# BT612-4.net
KiCad netlist of a schematic drawn in Altium Designer
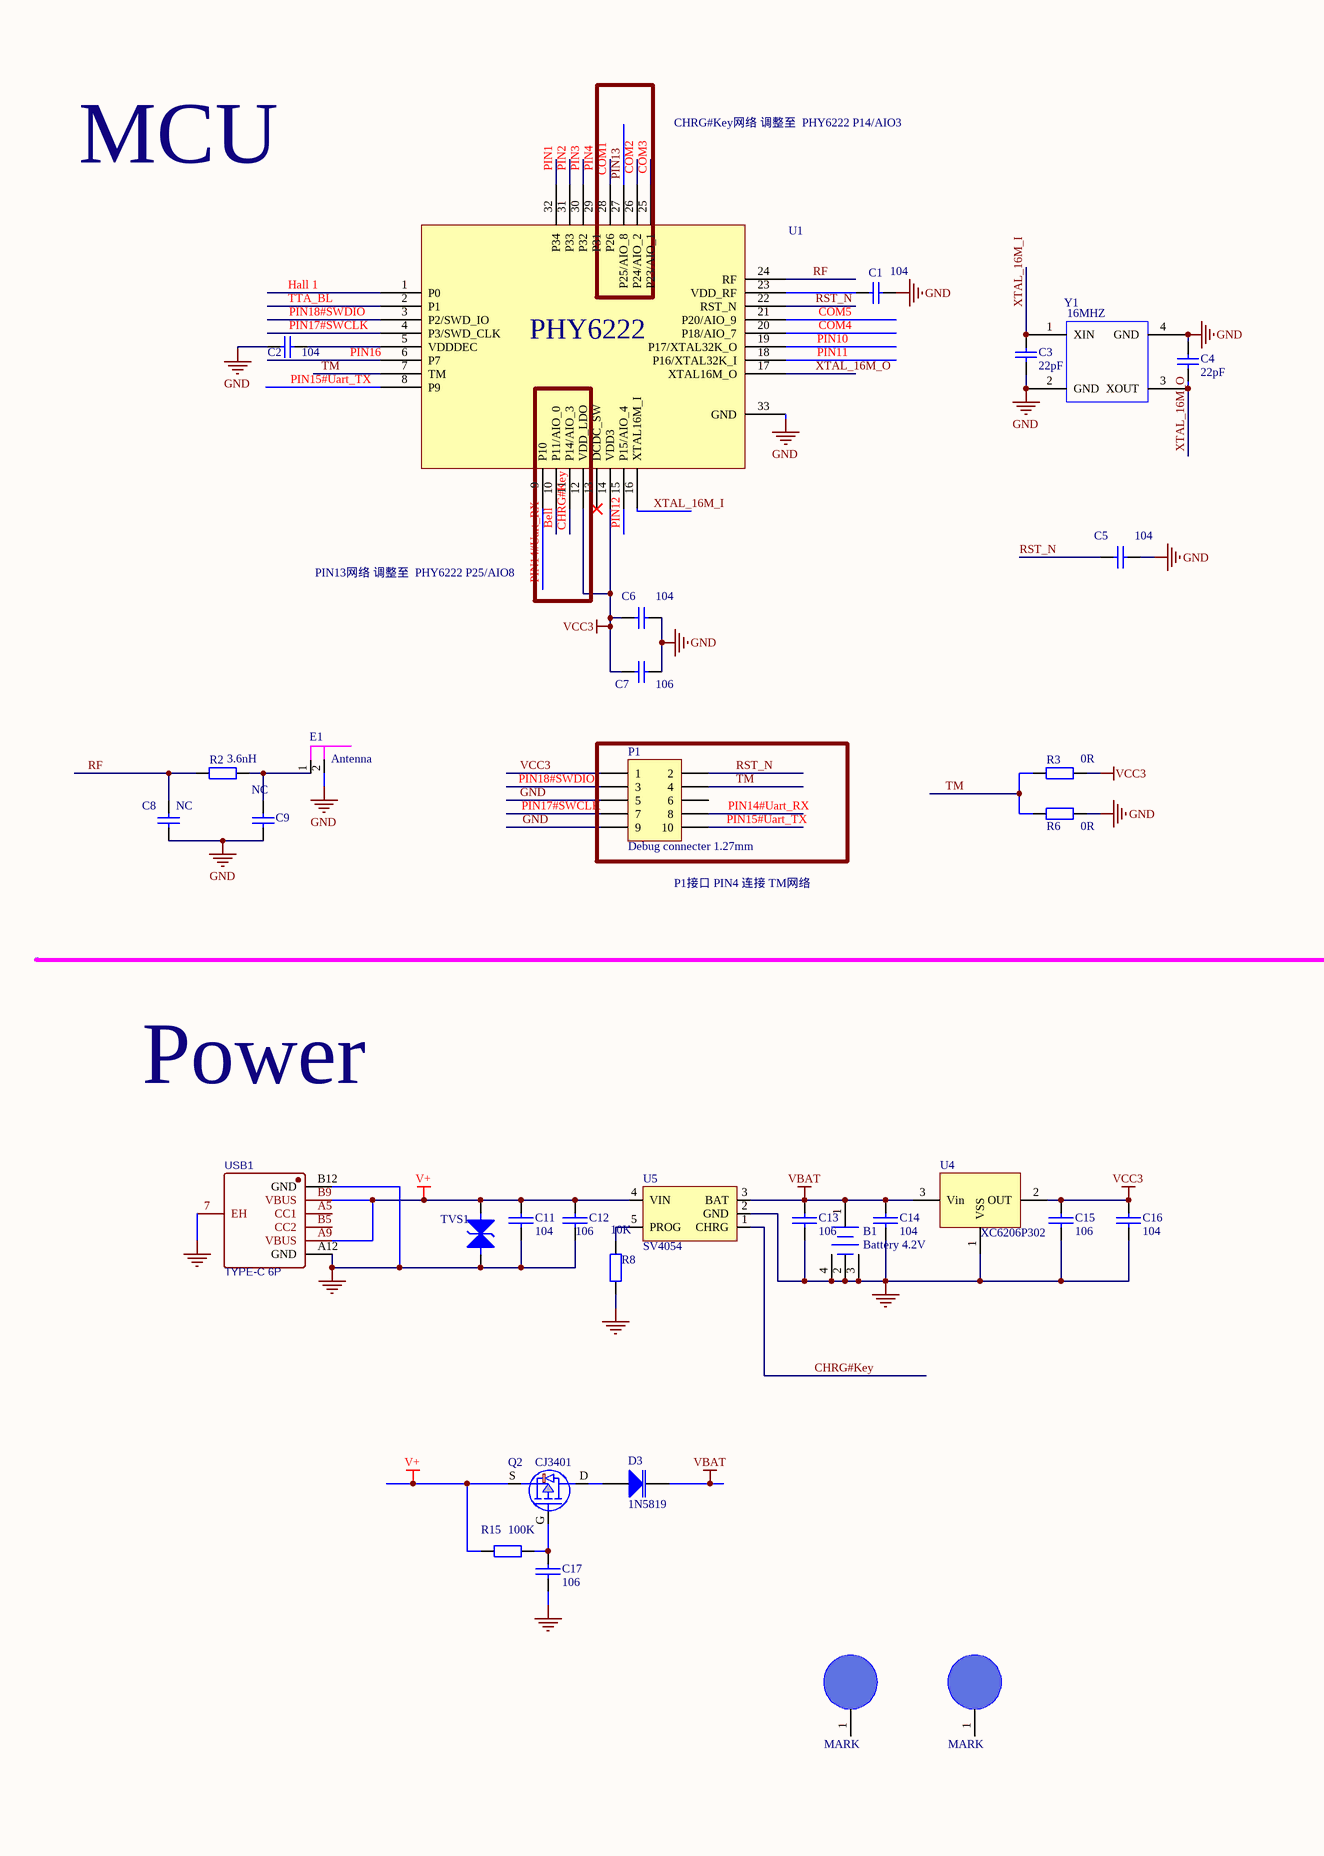
[diagram p0: BT612-4.SchDoc, left]
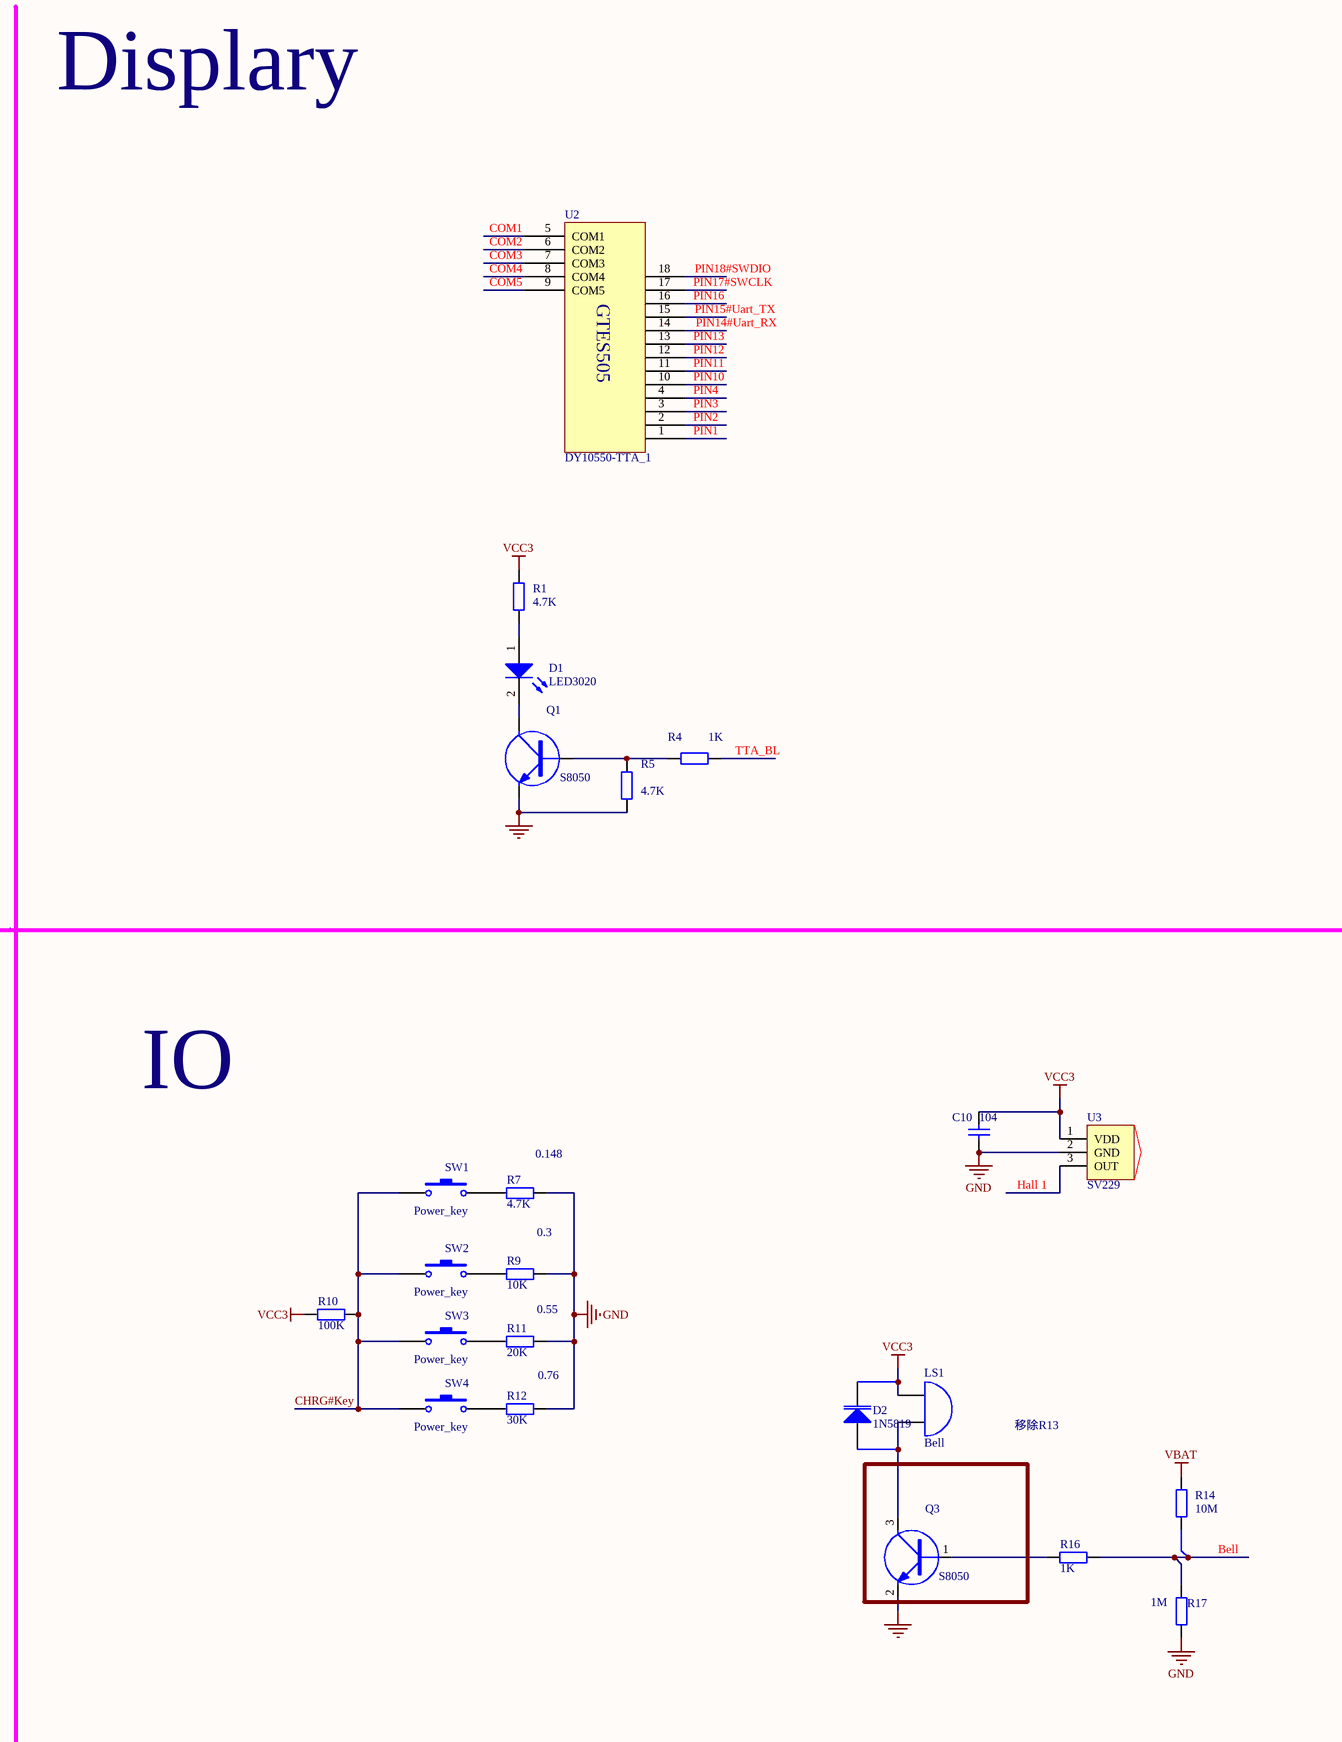
[diagram p1: BT612-4.SchDoc, right]

(export (version "E")
  (design (tool "Eeschema 10.0.6"))
  (components
    (comp (ref "B1")
      (value "Battery 4.2V")
      (footprint "BAT2P-1.25")
      (description "Multicell Battery")
      (fields (field (name "PUBLISHER") "Altium Limited"))
      (libsource (lib "SR4K_PHY6222_simplify_v1") (part "Battery"))
    )
    (comp (ref "C1")
      (value "104")
      (footprint "0402C")
      (description "Capacitor")
      (fields (field (name "PUBLISHER") "Altium Limited"))
      (libsource (lib "Miscellaneous Devices") (part "Cap"))
    )
    (comp (ref "C2")
      (value "104")
      (footprint "0402C")
      (description "Capacitor")
      (fields (field (name "PUBLISHER") "Altium Limited"))
      (libsource (lib "Miscellaneous Devices") (part "Cap"))
    )
    (comp (ref "C3")
      (value "22pF")
      (footprint "0402C")
      (description "Capacitor")
      (fields (field (name "PUBLISHER") "Altium Limited"))
      (libsource (lib "Miscellaneous Devices") (part "Cap"))
    )
    (comp (ref "C4")
      (value "22pF")
      (footprint "0402C")
      (description "Capacitor")
      (libsource (lib "Miscellaneous Devices") (part "Cap"))
    )
    (comp (ref "C5")
      (value "104")
      (footprint "0402C")
      (description "Capacitor")
      (fields (field (name "PUBLISHER") "Altium Limited"))
      (libsource (lib "Miscellaneous Devices") (part "Cap"))
    )
    (comp (ref "C6")
      (value "104")
      (footprint "0402C")
      (description "Capacitor")
      (fields (field (name "PUBLISHER") "Altium Limited"))
      (libsource (lib "Miscellaneous Devices") (part "Cap"))
    )
    (comp (ref "C7")
      (value "106")
      (footprint "0603-C")
      (description "Capacitor")
      (fields (field (name "PUBLISHER") "Altium Limited"))
      (libsource (lib "Miscellaneous Devices") (part "Cap"))
    )
    (comp (ref "C8")
      (value "NC")
      (footprint "0402C")
      (description "Capacitor")
      (fields (field (name "PUBLISHER") "Altium Limited"))
      (libsource (lib "Miscellaneous Devices") (part "Cap"))
    )
    (comp (ref "C9")
      (value "NC")
      (footprint "0402C")
      (description "Capacitor")
      (fields (field (name "PUBLISHER") "Altium Limited"))
      (libsource (lib "Miscellaneous Devices") (part "Cap"))
    )
    (comp (ref "C10")
      (value "104")
      (footprint "0402C")
      (description "Capacitor")
      (fields (field (name "PUBLISHER") "Altium Limited"))
      (libsource (lib "Miscellaneous Devices") (part "Cap"))
    )
    (comp (ref "C11")
      (value "104")
      (footprint "0402C")
      (description "Capacitor")
      (libsource (lib "*") (part "CAP"))
    )
    (comp (ref "C12")
      (value "106")
      (footprint "0603-C")
      (description "Capacitor")
      (libsource (lib "*") (part "CAP"))
    )
    (comp (ref "C13")
      (value "106")
      (footprint "0603-C")
      (description "Capacitor")
      (libsource (lib "*") (part "CAP"))
    )
    (comp (ref "C14")
      (value "104")
      (footprint "0402C")
      (description "Capacitor")
      (libsource (lib "*") (part "CAP"))
    )
    (comp (ref "C15")
      (value "106")
      (footprint "0603-C")
      (description "Capacitor")
      (libsource (lib "*") (part "CAP"))
    )
    (comp (ref "C16")
      (value "104")
      (footprint "0402C")
      (description "Capacitor")
      (libsource (lib "*") (part "CAP"))
    )
    (comp (ref "C17")
      (value "106")
      (footprint "0603-C")
      (description "Capacitor")
      (libsource (lib "*") (part "CAP"))
    )
    (comp (ref "D1")
      (value "LED3020")
      (footprint "LED-3020")
      (description "Typical INFRARED GaAs LED")
      (fields (field (name "PUBLISHER") "Altium Limited"))
      (libsource (lib "Miscellaneous Devices") (part "LED0"))
    )
    (comp (ref "D2")
      (value "1N5819")
      (footprint "SOD323")
      (description "Variable Capacitance Diode")
      (fields (field (name "PUBLISHER") "Altium Limited"))
      (libsource (lib "Miscellaneous Devices") (part "D Varactor"))
    )
    (comp (ref "D3")
      (value "1N5819")
      (footprint "SOD323")
      (description "Variable Capacitance Diode")
      (fields (field (name "PUBLISHER") "Altium Limited"))
      (libsource (lib "Miscellaneous Devices") (part "D Varactor"))
    )
    (comp (ref "E1") (value "Antenna") (footprint "BT-ANT") (libsource (lib "Schlib") (part "Antenna")))
    (comp (ref "LS1")
      (value "Bell")
      (footprint "BUZZ-12085")
      (description "Electrical Bell")
      (fields (field (name "PUBLISHER") "Altium Limited"))
      (libsource (lib "Miscellaneous Devices") (part "Bell"))
    )
    (comp (ref "P1")
      (value "Debug connecter 1.27mm")
      (footprint "SIP5-X2-1.27")
      (description "Header, 5-Pin, Dual row")
      (fields (field (name "PUBLISHER") "Altium Limited"))
      (libsource (lib "Miscellaneous Connectors") (part "Header 5X2"))
    )
    (comp (ref "Q1")
      (value "S8050")
      (footprint "SOT23")
      (description "NPN Transistor")
      (libsource (lib "*") (part "NPN"))
    )
    (comp (ref "Q2") (value "CJ3401") (footprint "SOT-23-GSD") (libsource (lib "*") (part "P-MOS")))
    (comp (ref "Q3")
      (value "S8050")
      (footprint "SOT23")
      (description "NPN Transistor")
      (libsource (lib "") (part "NPN_1"))
    )
    (comp (ref "R1")
      (value "4.7K")
      (footprint "0402R")
      (description "Resistor")
      (fields (field (name "PUBLISHER") "Altium Limited"))
      (libsource (lib "") (part "Res2_1"))
    )
    (comp (ref "R2")
      (value "3.6nH")
      (footprint "0402R")
      (description "Resistor")
      (fields (field (name "PUBLISHER") "Altium Limited"))
      (libsource (lib "") (part "Res2_2"))
    )
    (comp (ref "R3")
      (value "0R")
      (footprint "0402R")
      (description "Resistor")
      (fields (field (name "PUBLISHER") "Altium Limited"))
      (libsource (lib "") (part "Res2_2"))
    )
    (comp (ref "R4")
      (value "1K")
      (footprint "0402R")
      (description "Resistor")
      (fields (field (name "PUBLISHER") "Altium Limited"))
      (libsource (lib "Miscellaneous Devices") (part "Res2"))
    )
    (comp (ref "R5")
      (value "4.7K")
      (footprint "0402R")
      (description "Resistor")
      (fields (field (name "PUBLISHER") "Altium Limited"))
      (libsource (lib "") (part "Res2_1"))
    )
    (comp (ref "R6")
      (value "0R")
      (footprint "0402R")
      (description "Resistor")
      (fields (field (name "PUBLISHER") "Altium Limited"))
      (libsource (lib "") (part "Res2_2"))
    )
    (comp (ref "R7")
      (value "4.7K")
      (footprint "0402R")
      (description "Resistor")
      (fields (field (name "PUBLISHER") "Altium Limited"))
      (libsource (lib "Miscellaneous Devices") (part "Res2"))
    )
    (comp (ref "R8")
      (value "10K")
      (footprint "0402R")
      (description "1%@100mA")
      (fields (field (name "PUBLISHER") "Altium Limited"))
      (libsource (lib "") (part "Res2_1"))
    )
    (comp (ref "R9")
      (value "10K")
      (footprint "0402R")
      (description "Resistor")
      (fields (field (name "PUBLISHER") "Altium Limited"))
      (libsource (lib "Miscellaneous Devices") (part "Res2"))
    )
    (comp (ref "R10")
      (value "100K")
      (footprint "0402R")
      (description "Resistor")
      (fields (field (name "PUBLISHER") "Altium Limited"))
      (libsource (lib "Miscellaneous Devices") (part "Res2"))
    )
    (comp (ref "R11")
      (value "20K")
      (footprint "0402R")
      (description "Resistor")
      (fields (field (name "PUBLISHER") "Altium Limited"))
      (libsource (lib "Miscellaneous Devices") (part "Res2"))
    )
    (comp (ref "R12")
      (value "30K")
      (footprint "0402R")
      (description "Resistor")
      (fields (field (name "PUBLISHER") "Altium Limited"))
      (libsource (lib "Miscellaneous Devices") (part "Res2"))
    )
    (comp (ref "R14")
      (value "10M")
      (footprint "0402R")
      (description "Resistor")
      (fields (field (name "PUBLISHER") "Altium Limited"))
      (libsource (lib "") (part "Res2_1"))
    )
    (comp (ref "R15")
      (value "100K")
      (footprint "0402R")
      (description "1%@100mA")
      (fields (field (name "PUBLISHER") "Altium Limited"))
      (libsource (lib "") (part "Res2_2"))
    )
    (comp (ref "R16")
      (value "1K")
      (footprint "0402R")
      (description "Resistor")
      (fields (field (name "PUBLISHER") "Altium Limited"))
      (libsource (lib "Miscellaneous Devices") (part "Res2"))
    )
    (comp (ref "R17")
      (value "1M")
      (footprint "0402R")
      (description "Resistor")
      (fields (field (name "PUBLISHER") "Altium Limited"))
      (libsource (lib "") (part "Res2_1"))
    )
    (comp (ref "SW1")
      (value "Power_key")
      (footprint "SW_PB_SMD_4X4")
      (description "Switch")
      (fields (field (name "PUBLISHER") "Altium Limited"))
      (libsource (lib "Miscellaneous Devices") (part "SW-PB"))
    )
    (comp (ref "SW2")
      (value "Power_key")
      (footprint "SW_PB_SMD_4X4")
      (description "Switch")
      (fields (field (name "PUBLISHER") "Altium Limited"))
      (libsource (lib "Miscellaneous Devices") (part "SW-PB"))
    )
    (comp (ref "SW3")
      (value "Power_key")
      (footprint "SW_PB_SMD_4X4")
      (description "Switch")
      (fields (field (name "PUBLISHER") "Altium Limited"))
      (libsource (lib "Miscellaneous Devices") (part "SW-PB"))
    )
    (comp (ref "SW4")
      (value "Power_key")
      (footprint "SW_PB_SMD_4X4")
      (description "Switch")
      (fields (field (name "PUBLISHER") "Altium Limited"))
      (libsource (lib "Miscellaneous Devices") (part "SW-PB"))
    )
    (comp (ref "TP1") (value "MARK") (footprint "MARK") (libsource (lib "BT612-4") (part "TP")))
    (comp (ref "TP2") (value "MARK") (footprint "MARK") (libsource (lib "BT612-4") (part "TP")))
    (comp (ref "TVS1") (value "TVS") (footprint "SOD323") (libsource (lib "*") (part "TVS")))
    (comp (ref "U1")
      (value "PHY6222")
      (footprint "QFN32-4*4")
      (libsource (lib "SR4K_PHY6222_simplify_v1") (part "PHY6222"))
    )
    (comp (ref "U2")
      (value "DY10550-TTA_1")
      (footprint "GTES505液晶屏")
      (libsource (lib "BT612-4") (part "DY10550-TTA_1"))
    )
    (comp (ref "U3") (value "SV229") (footprint "SOT23-3") (libsource (lib "*") (part "霍尔44E 938")))
    (comp (ref "U4") (value "XC6206P302") (footprint "SOT23") (libsource (lib "*") (part "XC6206P302")))
    (comp (ref "U5") (value "SV4054") (footprint "SOT23-5") (libsource (lib "*") (part "SV4054")))
    (comp (ref "USB1")
      (value "TYPE-C 6P")
      (footprint "TYPE-C 6P")
      (fields (field (name "BOM_SUPPLIER PART") "C456012") (field (name "CONTRIBUTOR") "LCSC"))
      (libsource (lib "altium-import") (part "root_0_mirrored_TYPE-C 6P_"))
    )
    (comp (ref "Y1") (value "16MHZ") (footprint "JZ-3225") (libsource (lib "*") (part "X1_1")))
  )
  (nets
    (net (code "1") (name "/Bell") (class "Default")
      (node (ref "R14") (pin "1") (pinfunction "1_1") (pintype "passive"))
      (node (ref "R16") (pin "2") (pinfunction "2_2") (pintype "passive"))
      (node (ref "R17") (pin "2") (pinfunction "2_2") (pintype "passive"))
      (node (ref "U1") (pin "10") (pinfunction "P11/AIO_0_10") (pintype "passive"))
    )
    (net (code "2") (name "/CHRG#Key") (class "Default")
      (node (ref "R10") (pin "2") (pinfunction "2_2") (pintype "passive"))
      (node (ref "SW1") (pin "1") (pinfunction "1_1") (pintype "passive"))
      (node (ref "SW2") (pin "1") (pinfunction "1_1") (pintype "passive"))
      (node (ref "SW3") (pin "1") (pinfunction "1_1") (pintype "passive"))
      (node (ref "SW4") (pin "1") (pinfunction "1_1") (pintype "passive"))
      (node (ref "U1") (pin "11") (pinfunction "P14/AIO_3_11") (pintype "passive"))
      (node (ref "U5") (pin "1") (pinfunction "CHRG_1") (pintype "passive"))
    )
    (net (code "3") (name "/COM1") (class "Default")
      (node (ref "U1") (pin "28") (pinfunction "P26_28") (pintype "passive"))
      (node (ref "U2") (pin "5") (pinfunction "COM1_5") (pintype "passive"))
    )
    (net (code "4") (name "/COM2") (class "Default")
      (node (ref "U1") (pin "26") (pinfunction "P24/AIO_2_26") (pintype "passive"))
      (node (ref "U2") (pin "6") (pinfunction "COM2_6") (pintype "passive"))
    )
    (net (code "5") (name "/COM3") (class "Default")
      (node (ref "U1") (pin "25") (pinfunction "P23/AIO_1_25") (pintype "passive"))
      (node (ref "U2") (pin "7") (pinfunction "COM3_7") (pintype "passive"))
    )
    (net (code "6") (name "/COM4") (class "Default")
      (node (ref "U1") (pin "20") (pinfunction "P18/AIO_7_20") (pintype "passive"))
      (node (ref "U2") (pin "8") (pinfunction "COM4_8") (pintype "passive"))
    )
    (net (code "7") (name "/COM5") (class "Default")
      (node (ref "U1") (pin "21") (pinfunction "P20/AIO_9_21") (pintype "passive"))
      (node (ref "U2") (pin "9") (pinfunction "COM5_9") (pintype "passive"))
    )
    (net (code "8") (name "/Hall 1") (class "Default")
      (node (ref "U1") (pin "1") (pinfunction "P0_1") (pintype "passive"))
      (node (ref "U3") (pin "3") (pinfunction "OUT_3") (pintype "passive"))
    )
    (net (code "9") (name "/PIN1") (class "Default")
      (node (ref "U1") (pin "32") (pinfunction "P34_32") (pintype "passive"))
      (node (ref "U2") (pin "1") (pintype "passive"))
    )
    (net (code "10") (name "/PIN2") (class "Default")
      (node (ref "U1") (pin "31") (pinfunction "P33_31") (pintype "passive"))
      (node (ref "U2") (pin "2") (pintype "passive"))
    )
    (net (code "11") (name "/PIN3") (class "Default")
      (node (ref "U1") (pin "30") (pinfunction "P32_30") (pintype "passive"))
      (node (ref "U2") (pin "3") (pintype "passive"))
    )
    (net (code "12") (name "/PIN4") (class "Default")
      (node (ref "U1") (pin "29") (pinfunction "P31_29") (pintype "passive"))
      (node (ref "U2") (pin "4") (pintype "passive"))
    )
    (net (code "13") (name "/PIN10") (class "Default")
      (node (ref "U1") (pin "19") (pinfunction "P17/XTAL32K_O_19") (pintype "passive"))
      (node (ref "U2") (pin "10") (pintype "passive"))
    )
    (net (code "14") (name "/PIN11") (class "Default")
      (node (ref "U1") (pin "18") (pinfunction "P16/XTAL32K_I_18") (pintype "passive"))
      (node (ref "U2") (pin "11") (pintype "passive"))
    )
    (net (code "15") (name "/PIN12") (class "Default")
      (node (ref "U1") (pin "15") (pinfunction "P15/AIO_4_15") (pintype "passive"))
      (node (ref "U2") (pin "12") (pintype "passive"))
    )
    (net (code "16") (name "/PIN13") (class "Default")
      (node (ref "U1") (pin "27") (pinfunction "P25/AIO_8_27") (pintype "passive"))
      (node (ref "U2") (pin "13") (pintype "passive"))
    )
    (net (code "17") (name "/PIN14#Uart_RX") (class "Default")
      (node (ref "P1") (pin "8") (pinfunction "8_8") (pintype "passive"))
      (node (ref "U1") (pin "9") (pinfunction "P10_9") (pintype "passive"))
      (node (ref "U2") (pin "14") (pintype "passive"))
    )
    (net (code "18") (name "/PIN15#Uart_TX") (class "Default")
      (node (ref "P1") (pin "10") (pinfunction "10_10") (pintype "passive"))
      (node (ref "U1") (pin "8") (pinfunction "P9_8") (pintype "passive"))
      (node (ref "U2") (pin "15") (pintype "passive"))
    )
    (net (code "19") (name "/PIN16") (class "Default")
      (node (ref "U1") (pin "6") (pinfunction "P7_6") (pintype "passive"))
      (node (ref "U2") (pin "16") (pintype "passive"))
    )
    (net (code "20") (name "/PIN17#SWCLK") (class "Default")
      (node (ref "P1") (pin "7") (pinfunction "7_7") (pintype "passive"))
      (node (ref "U1") (pin "4") (pinfunction "P3/SWD_CLK_4") (pintype "passive"))
      (node (ref "U2") (pin "17") (pintype "passive"))
    )
    (net (code "21") (name "/PIN18#SWDIO") (class "Default")
      (node (ref "P1") (pin "3") (pinfunction "3_3") (pintype "passive"))
      (node (ref "U1") (pin "3") (pinfunction "P2/SWD_IO_3") (pintype "passive"))
      (node (ref "U2") (pin "18") (pintype "passive"))
    )
    (net (code "22") (name "/RF") (class "Default")
      (node (ref "C8") (pin "1") (pinfunction "1_1") (pintype "passive"))
      (node (ref "R2") (pin "2") (pinfunction "2_2") (pintype "passive"))
      (node (ref "U1") (pin "24") (pinfunction "RF_24") (pintype "passive"))
    )
    (net (code "23") (name "/RST_N") (class "Default")
      (node (ref "C5") (pin "1") (pinfunction "1_1") (pintype "passive"))
      (node (ref "P1") (pin "2") (pinfunction "2_2") (pintype "passive"))
      (node (ref "U1") (pin "22") (pinfunction "RST_N_22") (pintype "passive"))
    )
    (net (code "24") (name "/TM") (class "Default")
      (node (ref "P1") (pin "4") (pinfunction "4_4") (pintype "passive"))
      (node (ref "R3") (pin "2") (pinfunction "2_2") (pintype "passive"))
      (node (ref "R6") (pin "2") (pinfunction "2_2") (pintype "passive"))
      (node (ref "U1") (pin "7") (pinfunction "TM_7") (pintype "passive"))
    )
    (net (code "25") (name "/TTA_BL") (class "Default")
      (node (ref "R4") (pin "2") (pinfunction "2_2") (pintype "passive"))
      (node (ref "U1") (pin "2") (pinfunction "P1_2") (pintype "passive"))
    )
    (net (code "26") (name "/XTAL_16M_I") (class "Default")
      (node (ref "C3") (pin "1") (pinfunction "1_1") (pintype "passive"))
      (node (ref "U1") (pin "16") (pinfunction "XTAL16M_I_16") (pintype "passive"))
      (node (ref "Y1") (pin "1") (pinfunction "XIN_1") (pintype "passive"))
    )
    (net (code "27") (name "/XTAL_16M_O") (class "Default")
      (node (ref "C4") (pin "2") (pinfunction "2_2") (pintype "passive"))
      (node (ref "U1") (pin "17") (pinfunction "XTAL16M_O_17") (pintype "passive"))
      (node (ref "Y1") (pin "3") (pinfunction "XOUT_3") (pintype "passive"))
    )
    (net (code "28") (name "GND") (class "Default")
      (node (ref "B1") (pin "2") (pinfunction "-_2") (pintype "passive"))
      (node (ref "B1") (pin "3") (pinfunction "3_3") (pintype "passive"))
      (node (ref "B1") (pin "4") (pinfunction "4_4") (pintype "passive"))
      (node (ref "C1") (pin "2") (pinfunction "2_2") (pintype "passive"))
      (node (ref "C10") (pin "2") (pinfunction "2_2") (pintype "passive"))
      (node (ref "C11") (pin "1") (pinfunction "1_1") (pintype "passive"))
      (node (ref "C12") (pin "1") (pinfunction "1_1") (pintype "passive"))
      (node (ref "C13") (pin "1") (pinfunction "1_1") (pintype "passive"))
      (node (ref "C14") (pin "1") (pinfunction "1_1") (pintype "passive"))
      (node (ref "C15") (pin "1") (pinfunction "1_1") (pintype "passive"))
      (node (ref "C16") (pin "1") (pinfunction "1_1") (pintype "passive"))
      (node (ref "C17") (pin "1") (pinfunction "1_1") (pintype "passive"))
      (node (ref "C2") (pin "1") (pinfunction "1_1") (pintype "passive"))
      (node (ref "C3") (pin "2") (pinfunction "2_2") (pintype "passive"))
      (node (ref "C4") (pin "1") (pinfunction "1_1") (pintype "passive"))
      (node (ref "C5") (pin "2") (pinfunction "2_2") (pintype "passive"))
      (node (ref "C6") (pin "2") (pinfunction "2_2") (pintype "passive"))
      (node (ref "C7") (pin "2") (pinfunction "2_2") (pintype "passive"))
      (node (ref "C8") (pin "2") (pinfunction "2_2") (pintype "passive"))
      (node (ref "C9") (pin "2") (pinfunction "2_2") (pintype "passive"))
      (node (ref "E1") (pin "2") (pinfunction "2_2") (pintype "passive"))
      (node (ref "P1") (pin "5") (pinfunction "5_5") (pintype "passive"))
      (node (ref "P1") (pin "9") (pinfunction "9_9") (pintype "passive"))
      (node (ref "Q1") (pin "2") (pinfunction "E_2") (pintype "passive"))
      (node (ref "Q3") (pin "2") (pinfunction "E_2") (pintype "passive"))
      (node (ref "R11") (pin "2") (pinfunction "2_2") (pintype "passive"))
      (node (ref "R12") (pin "2") (pinfunction "2_2") (pintype "passive"))
      (node (ref "R17") (pin "1") (pinfunction "1_1") (pintype "passive"))
      (node (ref "R5") (pin "1") (pinfunction "1_1") (pintype "passive"))
      (node (ref "R6") (pin "1") (pinfunction "1_1") (pintype "passive"))
      (node (ref "R7") (pin "2") (pinfunction "2_2") (pintype "passive"))
      (node (ref "R8") (pin "1") (pinfunction "1_1") (pintype "passive"))
      (node (ref "R9") (pin "2") (pinfunction "2_2") (pintype "passive"))
      (node (ref "TVS1") (pin "1") (pinfunction "1_1") (pintype "passive"))
      (node (ref "U1") (pin "33") (pinfunction "GND_33") (pintype "power_in"))
      (node (ref "U3") (pin "2") (pinfunction "GND_2") (pintype "passive"))
      (node (ref "U4") (pin "1") (pinfunction "VSS_1") (pintype "passive"))
      (node (ref "U5") (pin "2") (pinfunction "GND_2") (pintype "passive"))
      (node (ref "USB1") (pin "7") (pinfunction "EH_7") (pintype "passive"))
      (node (ref "USB1") (pin "A12") (pinfunction "GND_A12") (pintype "passive"))
      (node (ref "USB1") (pin "B12") (pinfunction "GND_B12") (pintype "passive"))
      (node (ref "Y1") (pin "2") (pinfunction "GND_2") (pintype "power_in"))
      (node (ref "Y1") (pin "4") (pinfunction "GND_4") (pintype "power_in"))
    )
    (net (code "29") (name "Net-(C9-Pad1)") (class "Default")
      (node (ref "C9") (pin "1") (pinfunction "1_1") (pintype "passive"))
      (node (ref "E1") (pin "1") (pinfunction "1_1") (pintype "passive"))
      (node (ref "R2") (pin "1") (pinfunction "1_1") (pintype "passive"))
    )
    (net (code "30") (name "Net-(D1-A)") (class "Default")
      (node (ref "D1") (pin "1") (pinfunction "A_1") (pintype "passive"))
      (node (ref "R1") (pin "1") (pinfunction "1_1") (pintype "passive"))
    )
    (net (code "31") (name "Net-(D1-K)") (class "Default")
      (node (ref "D1") (pin "2") (pinfunction "K_2") (pintype "passive"))
      (node (ref "Q1") (pin "3") (pinfunction "C_3") (pintype "passive"))
    )
    (net (code "32") (name "Net-(LS1-B)") (class "Default")
      (node (ref "D2") (pin "1") (pinfunction "1_1") (pintype "passive"))
      (node (ref "LS1") (pin "2") (pinfunction "B_2") (pintype "passive"))
      (node (ref "Q3") (pin "3") (pinfunction "C_3") (pintype "passive"))
    )
    (net (code "33") (name "Net-(Q1-B)") (class "Default")
      (node (ref "Q1") (pin "1") (pinfunction "B_1") (pintype "passive"))
      (node (ref "R4") (pin "1") (pinfunction "1_1") (pintype "passive"))
      (node (ref "R5") (pin "2") (pinfunction "2_2") (pintype "passive"))
    )
    (net (code "34") (name "Net-(Q2-DRAIN)") (class "Default")
      (node (ref "D3") (pin "1") (pinfunction "1_1") (pintype "passive"))
      (node (ref "Q2") (pin "D") (pinfunction "DRAIN_D") (pintype "passive"))
    )
    (net (code "35") (name "Net-(Q2-GATE)") (class "Default")
      (node (ref "C17") (pin "2") (pinfunction "2_2") (pintype "passive"))
      (node (ref "Q2") (pin "G") (pinfunction "GATE_G") (pintype "passive"))
      (node (ref "R15") (pin "1") (pinfunction "1_1") (pintype "passive"))
    )
    (net (code "36") (name "Net-(Q3-B)") (class "Default")
      (node (ref "Q3") (pin "1") (pinfunction "B_1") (pintype "passive"))
      (node (ref "R16") (pin "1") (pinfunction "1_1") (pintype "passive"))
    )
    (net (code "37") (name "Net-(R7-Pad1)") (class "Default")
      (node (ref "R7") (pin "1") (pinfunction "1_1") (pintype "passive"))
      (node (ref "SW1") (pin "2") (pinfunction "2_2") (pintype "passive"))
    )
    (net (code "38") (name "Net-(R9-Pad1)") (class "Default")
      (node (ref "R9") (pin "1") (pinfunction "1_1") (pintype "passive"))
      (node (ref "SW2") (pin "2") (pinfunction "2_2") (pintype "passive"))
    )
    (net (code "39") (name "Net-(R11-Pad1)") (class "Default")
      (node (ref "R11") (pin "1") (pinfunction "1_1") (pintype "passive"))
      (node (ref "SW3") (pin "2") (pinfunction "2_2") (pintype "passive"))
    )
    (net (code "40") (name "Net-(R12-Pad1)") (class "Default")
      (node (ref "R12") (pin "1") (pinfunction "1_1") (pintype "passive"))
      (node (ref "SW4") (pin "2") (pinfunction "2_2") (pintype "passive"))
    )
    (net (code "41") (name "Net-(U1-VDDDEC)") (class "Default")
      (node (ref "C2") (pin "2") (pinfunction "2_2") (pintype "passive"))
      (node (ref "U1") (pin "5") (pinfunction "VDDDEC_5") (pintype "power_in"))
    )
    (net (code "42") (name "Net-(U1-VDD_RF)") (class "Default")
      (node (ref "C1") (pin "1") (pinfunction "1_1") (pintype "passive"))
      (node (ref "U1") (pin "23") (pinfunction "VDD_RF_23") (pintype "power_in"))
    )
    (net (code "43") (name "Net-(U5-PROG)") (class "Default")
      (node (ref "R8") (pin "2") (pinfunction "2_2") (pintype "passive"))
      (node (ref "U5") (pin "5") (pinfunction "PROG_5") (pintype "passive"))
    )
    (net (code "44") (name "V+") (class "Default")
      (node (ref "C11") (pin "2") (pinfunction "2_2") (pintype "passive"))
      (node (ref "C12") (pin "2") (pinfunction "2_2") (pintype "passive"))
      (node (ref "Q2") (pin "S") (pinfunction "SOURCE_S") (pintype "passive"))
      (node (ref "R15") (pin "2") (pinfunction "2_2") (pintype "passive"))
      (node (ref "TVS1") (pin "2") (pinfunction "2_2") (pintype "passive"))
      (node (ref "U5") (pin "4") (pinfunction "VIN_4") (pintype "passive"))
      (node (ref "USB1") (pin "A9") (pinfunction "VBUS_A9") (pintype "passive"))
      (node (ref "USB1") (pin "B9") (pinfunction "VBUS_B9") (pintype "passive"))
    )
    (net (code "45") (name "VBAT") (class "Default")
      (node (ref "B1") (pin "1") (pinfunction "+_1") (pintype "passive"))
      (node (ref "C13") (pin "2") (pinfunction "2_2") (pintype "passive"))
      (node (ref "C14") (pin "2") (pinfunction "2_2") (pintype "passive"))
      (node (ref "D3") (pin "2") (pinfunction "2_2") (pintype "passive"))
      (node (ref "R14") (pin "2") (pinfunction "2_2") (pintype "passive"))
      (node (ref "U4") (pin "3") (pinfunction "Vin_3") (pintype "passive"))
      (node (ref "U5") (pin "3") (pinfunction "BAT_3") (pintype "passive"))
    )
    (net (code "46") (name "VCC3") (class "Default")
      (node (ref "C10") (pin "1") (pinfunction "1_1") (pintype "passive"))
      (node (ref "C15") (pin "2") (pinfunction "2_2") (pintype "passive"))
      (node (ref "C16") (pin "2") (pinfunction "2_2") (pintype "passive"))
      (node (ref "C6") (pin "1") (pinfunction "1_1") (pintype "passive"))
      (node (ref "C7") (pin "1") (pinfunction "1_1") (pintype "passive"))
      (node (ref "D2") (pin "2") (pinfunction "2_2") (pintype "passive"))
      (node (ref "LS1") (pin "1") (pinfunction "A_1") (pintype "passive"))
      (node (ref "P1") (pin "1") (pinfunction "1_1") (pintype "passive"))
      (node (ref "R1") (pin "2") (pinfunction "2_2") (pintype "passive"))
      (node (ref "R10") (pin "1") (pinfunction "1_1") (pintype "passive"))
      (node (ref "R3") (pin "1") (pinfunction "1_1") (pintype "passive"))
      (node (ref "U1") (pin "12") (pinfunction "VDD_LDO_12") (pintype "power_in"))
      (node (ref "U1") (pin "14") (pinfunction "VDD3_14") (pintype "power_in"))
      (node (ref "U3") (pin "1") (pinfunction "VDD_1") (pintype "passive"))
      (node (ref "U4") (pin "2") (pinfunction "OUT_2") (pintype "passive"))
    )
    (net (code "47") (name "unconnected-(P1-Pad6)") (class "Default")
      (node (ref "P1") (pin "6") (pinfunction "6_6") (pintype "passive"))
    )
    (net (code "48") (name "unconnected-(TP1-Pad1)") (class "Default")
      (node (ref "TP1") (pin "1") (pinfunction "1_1") (pintype "passive"))
    )
    (net (code "49") (name "unconnected-(TP2-Pad1)") (class "Default")
      (node (ref "TP2") (pin "1") (pinfunction "1_1") (pintype "passive"))
    )
    (net (code "50") (name "unconnected-(U1-DCDC_SW-Pad13)") (class "Default")
      (node (ref "U1") (pin "13") (pinfunction "DCDC_SW_13") (pintype "power_in+no_connect"))
    )
    (net (code "51") (name "unconnected-(USB1-CC1-PadA5)") (class "Default")
      (node (ref "USB1") (pin "A5") (pinfunction "CC1_A5") (pintype "passive"))
    )
    (net (code "52") (name "unconnected-(USB1-CC2-PadB5)") (class "Default")
      (node (ref "USB1") (pin "B5") (pinfunction "CC2_B5") (pintype "passive"))
    )
  )
)
